# common_power.net
KiCad netlist of a schematic drawn in Altium Designer
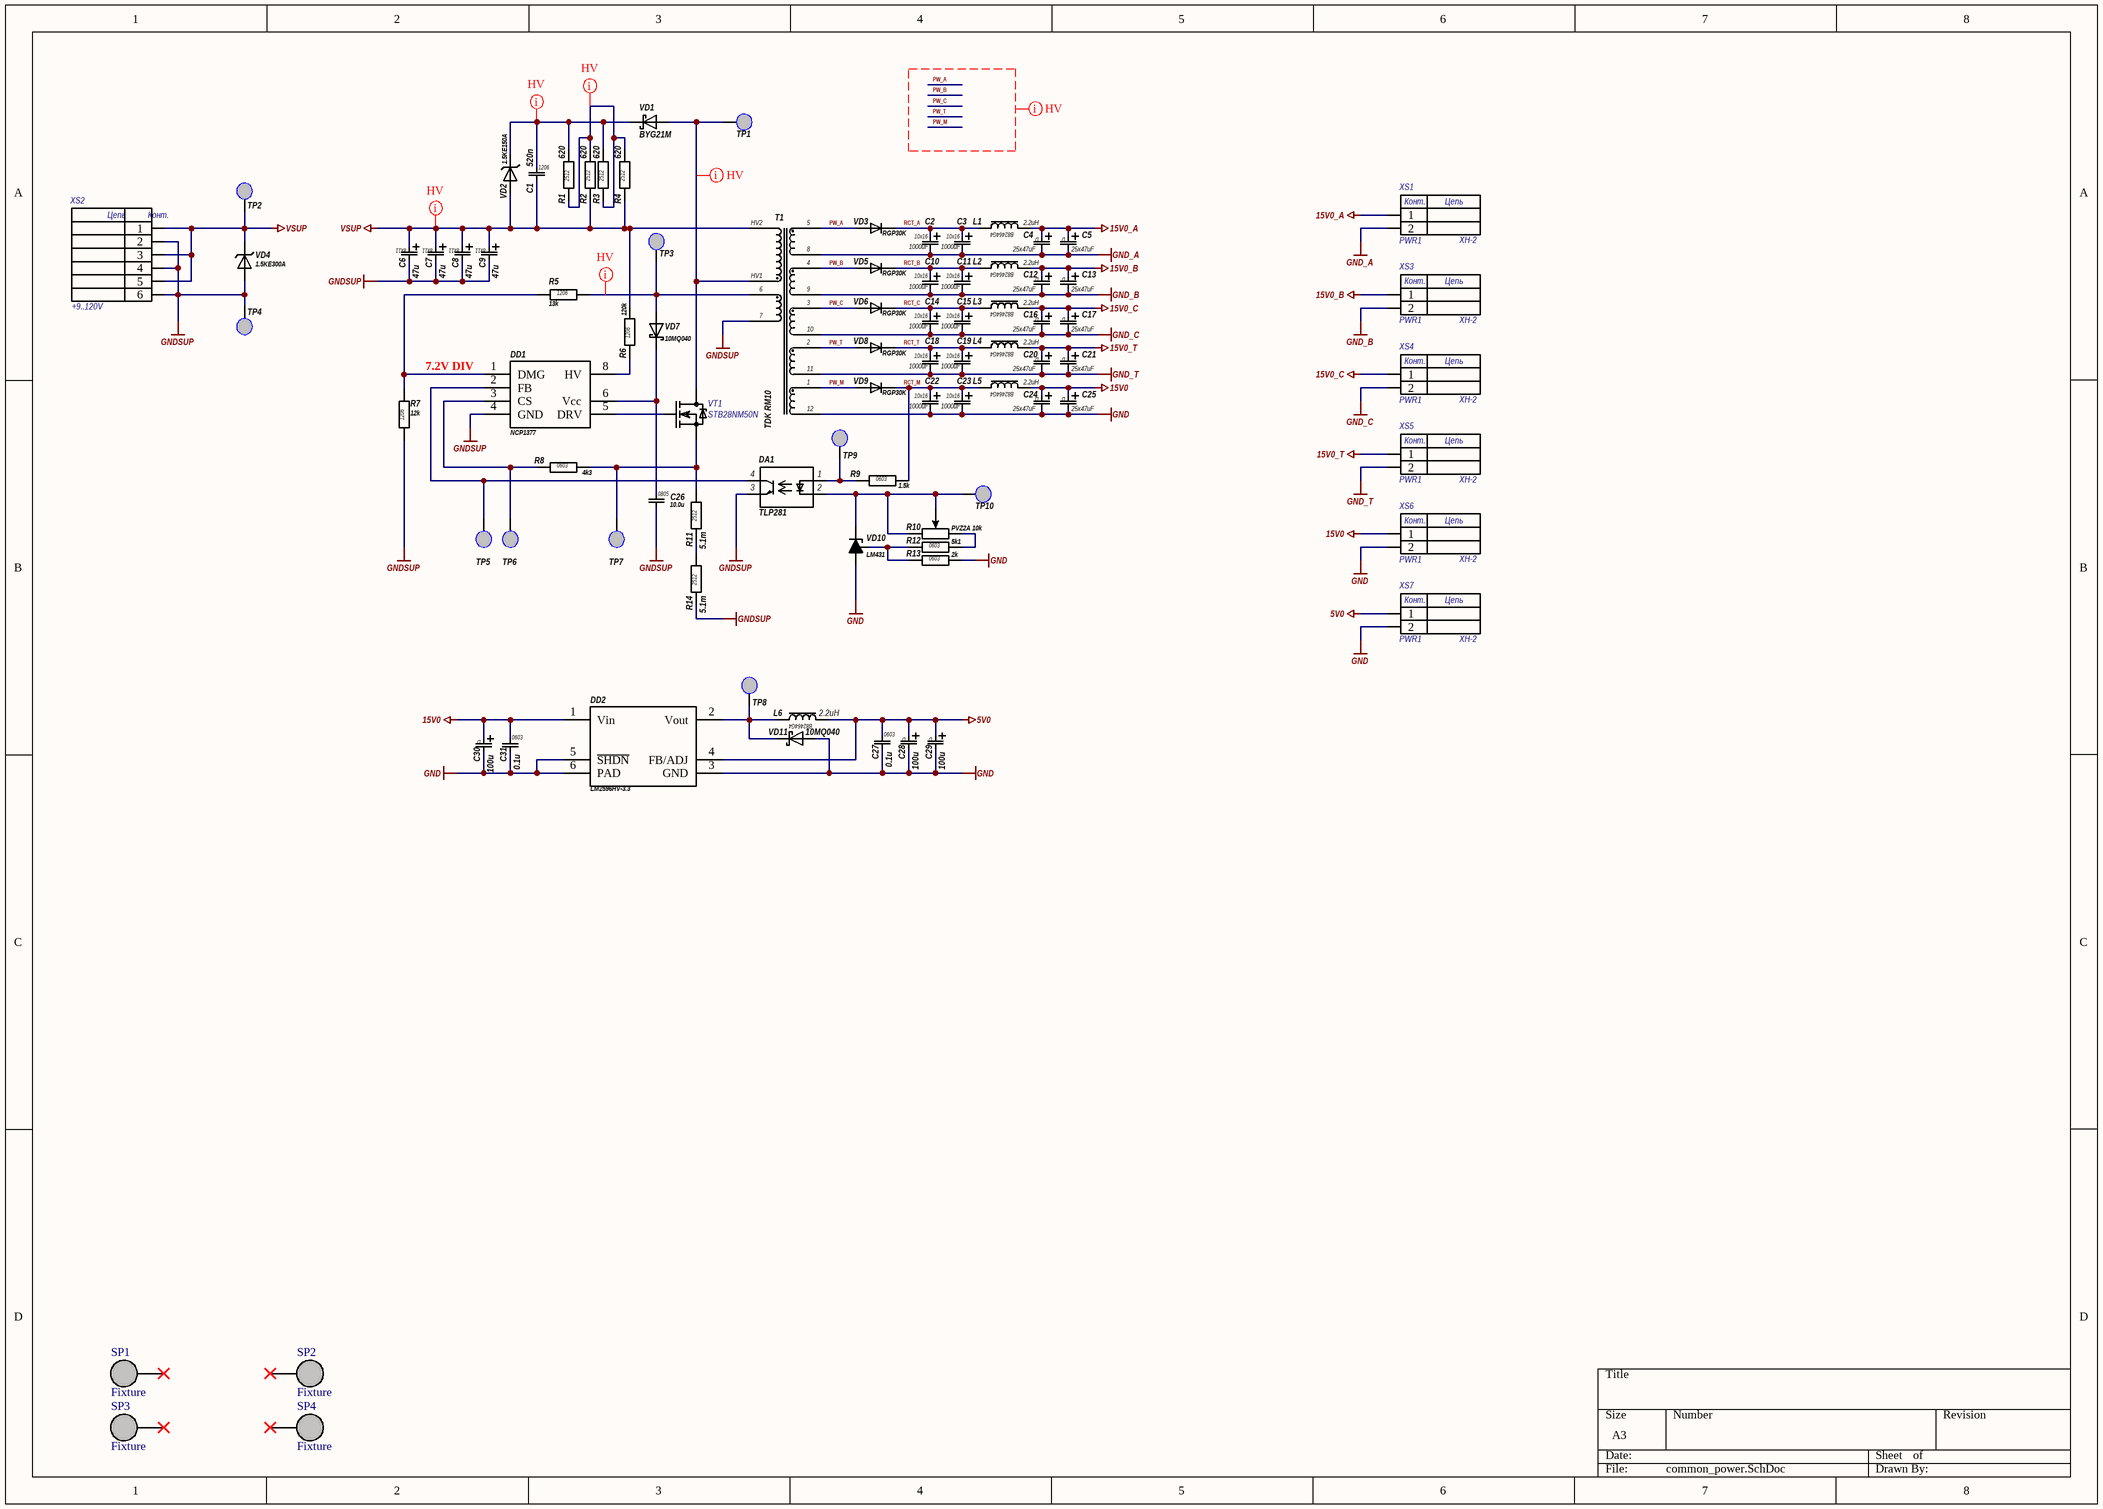
[diagram p0: common_power.SchDoc]

(export (version "E")
  (design (tool "Eeschema 10.0.6"))
  (components
    (comp (ref "C1")
      (value "520n")
      (footprint "CAP1206")
      (description "Конденсатор чип")
      (libsource (lib "EwgPassive") (part "CAP_1206"))
    )
    (comp (ref "C2")
      (value "1000uF")
      (footprint "ECAP_10x16")
      (description "Конденсатор электролитический")
      (libsource (lib "EwgPassive") (part "CAP_10x16"))
    )
    (comp (ref "C3")
      (value "1000uF")
      (footprint "ECAP_10x16")
      (description "Конденсатор электролитический")
      (libsource (lib "EwgPassive") (part "CAP_10x16"))
    )
    (comp (ref "C4")
      (value "25x47uF")
      (footprint "CAP_D")
      (description "Конденсатор танталовый")
      (libsource (lib "EwgPassive") (part "CAP_D"))
    )
    (comp (ref "C5")
      (value "25x47uF")
      (footprint "CAP_D")
      (description "Конденсатор танталовый")
      (libsource (lib "EwgPassive") (part "CAP_D"))
    )
    (comp (ref "C6")
      (value "47u")
      (footprint "B41828 8X11.5")
      (description "Конденсатор электролитический")
      (libsource (lib "EwgPassive") (part "CAP_B41828 8X11.5"))
    )
    (comp (ref "C7")
      (value "47u")
      (footprint "B41828 8X11.5")
      (description "Конденсатор электролитический")
      (libsource (lib "EwgPassive") (part "CAP_B41828 8X11.5"))
    )
    (comp (ref "C8")
      (value "47u")
      (footprint "B41828 8X11.5")
      (description "Конденсатор электролитический")
      (libsource (lib "EwgPassive") (part "CAP_B41828 8X11.5"))
    )
    (comp (ref "C9")
      (value "47u")
      (footprint "B41828 8X11.5")
      (description "Конденсатор электролитический")
      (libsource (lib "EwgPassive") (part "CAP_B41828 8X11.5"))
    )
    (comp (ref "C10")
      (value "1000uF")
      (footprint "ECAP_10x16")
      (description "Конденсатор электролитический")
      (libsource (lib "EwgPassive") (part "CAP_10x16"))
    )
    (comp (ref "C11")
      (value "1000uF")
      (footprint "ECAP_10x16")
      (description "Конденсатор электролитический")
      (libsource (lib "EwgPassive") (part "CAP_10x16"))
    )
    (comp (ref "C12")
      (value "25x47uF")
      (footprint "CAP_D")
      (description "Конденсатор танталовый")
      (libsource (lib "EwgPassive") (part "CAP_D"))
    )
    (comp (ref "C13")
      (value "25x47uF")
      (footprint "CAP_D")
      (description "Конденсатор танталовый")
      (libsource (lib "EwgPassive") (part "CAP_D"))
    )
    (comp (ref "C14")
      (value "1000uF")
      (footprint "ECAP_10x16")
      (description "Конденсатор электролитический")
      (libsource (lib "EwgPassive") (part "CAP_10x16"))
    )
    (comp (ref "C15")
      (value "1000uF")
      (footprint "ECAP_10x16")
      (description "Конденсатор электролитический")
      (libsource (lib "EwgPassive") (part "CAP_10x16"))
    )
    (comp (ref "C16")
      (value "25x47uF")
      (footprint "CAP_D")
      (description "Конденсатор танталовый")
      (libsource (lib "EwgPassive") (part "CAP_D"))
    )
    (comp (ref "C17")
      (value "25x47uF")
      (footprint "CAP_D")
      (description "Конденсатор танталовый")
      (libsource (lib "EwgPassive") (part "CAP_D"))
    )
    (comp (ref "C18")
      (value "1000uF")
      (footprint "ECAP_10x16")
      (description "Конденсатор электролитический")
      (libsource (lib "EwgPassive") (part "CAP_10x16"))
    )
    (comp (ref "C19")
      (value "1000uF")
      (footprint "ECAP_10x16")
      (description "Конденсатор электролитический")
      (libsource (lib "EwgPassive") (part "CAP_10x16"))
    )
    (comp (ref "C20")
      (value "25x47uF")
      (footprint "CAP_D")
      (description "Конденсатор танталовый")
      (libsource (lib "EwgPassive") (part "CAP_D"))
    )
    (comp (ref "C21")
      (value "25x47uF")
      (footprint "CAP_D")
      (description "Конденсатор танталовый")
      (libsource (lib "EwgPassive") (part "CAP_D"))
    )
    (comp (ref "C22")
      (value "1000uF")
      (footprint "ECAP_10x16")
      (description "Конденсатор электролитический")
      (libsource (lib "EwgPassive") (part "CAP_10x16"))
    )
    (comp (ref "C23")
      (value "1000uF")
      (footprint "ECAP_10x16")
      (description "Конденсатор электролитический")
      (libsource (lib "EwgPassive") (part "CAP_10x16"))
    )
    (comp (ref "C24")
      (value "25x47uF")
      (footprint "CAP_D")
      (description "Конденсатор танталовый")
      (libsource (lib "EwgPassive") (part "CAP_D"))
    )
    (comp (ref "C25")
      (value "25x47uF")
      (footprint "CAP_D")
      (description "Конденсатор танталовый")
      (libsource (lib "EwgPassive") (part "CAP_D"))
    )
    (comp (ref "C26")
      (value "10.0u")
      (footprint "CAP0805")
      (description "Конденсатор чип")
      (libsource (lib "EwgPassive") (part "CAP_0805"))
    )
    (comp (ref "C27")
      (value "0.1u")
      (footprint "CAP0603")
      (description "Конденсатор чип")
      (libsource (lib "EwgPassive") (part "CAP_0603"))
    )
    (comp (ref "C28")
      (value "100u")
      (footprint "CAP_D")
      (description "Конденсатор танталовый")
      (libsource (lib "EwgPassive") (part "CAP_D"))
    )
    (comp (ref "C29")
      (value "100u")
      (footprint "CAP_D")
      (description "Конденсатор танталовый")
      (libsource (lib "EwgPassive") (part "CAP_D"))
    )
    (comp (ref "C30")
      (value "100u")
      (footprint "CAP_D")
      (description "Конденсатор танталовый")
      (libsource (lib "EwgPassive") (part "CAP_D"))
    )
    (comp (ref "C31")
      (value "0.1u")
      (footprint "CAP0603")
      (description "Конденсатор чип")
      (libsource (lib "EwgPassive") (part "CAP_0603"))
    )
    (comp (ref "DA1")
      (value "TLP281")
      (footprint "SOIC-4")
      (description "Оптопара")
      (libsource (lib "EwgOpto") (part "TPL281-1"))
    )
    (comp (ref "DD1")
      (value "NCP1377")
      (footprint "SO8_NCP1377")
      (description "Контроллер обратноходового преобразователя")
      (libsource (lib "EwgMicrochips") (part "NCP1377"))
    )
    (comp (ref "DD2")
      (value "LM2596HV-3.3")
      (footprint "TO-263-5")
      (description "Понижающий DC-DC преобразователь с широким диапазоном входного напряжения (Vin=4.5..60V)")
      (libsource (lib "EwgMicrochips") (part "LM2596HV-x.x"))
    )
    (comp (ref "L1")
      (value "2.2uH")
      (footprint "B82464G4")
      (description "Индуктивность чип")
      (libsource (lib "EwgPassive") (part "IND_B82464G4"))
    )
    (comp (ref "L2")
      (value "2.2uH")
      (footprint "B82464G4")
      (description "Индуктивность чип")
      (libsource (lib "EwgPassive") (part "IND_B82464G4"))
    )
    (comp (ref "L3")
      (value "2.2uH")
      (footprint "B82464G4")
      (description "Индуктивность чип")
      (libsource (lib "EwgPassive") (part "IND_B82464G4"))
    )
    (comp (ref "L4")
      (value "2.2uH")
      (footprint "B82464G4")
      (description "Индуктивность чип")
      (libsource (lib "EwgPassive") (part "IND_B82464G4"))
    )
    (comp (ref "L5")
      (value "2.2uH")
      (footprint "B82464G4")
      (description "Индуктивность чип")
      (libsource (lib "EwgPassive") (part "IND_B82464G4"))
    )
    (comp (ref "L6")
      (value "2.2uH")
      (footprint "B82464G4")
      (description "Индуктивность чип")
      (libsource (lib "EwgPassive") (part "IND_B82464G4"))
    )
    (comp (ref "R1")
      (value "620")
      (footprint "RES2512")
      (description "Резистор чип")
      (libsource (lib "EwgPassive") (part "RES_2512"))
    )
    (comp (ref "R2")
      (value "620")
      (footprint "RES2512")
      (description "Резистор чип")
      (libsource (lib "EwgPassive") (part "RES_2512"))
    )
    (comp (ref "R3")
      (value "620")
      (footprint "RES2512")
      (description "Резистор чип")
      (libsource (lib "EwgPassive") (part "RES_2512"))
    )
    (comp (ref "R4")
      (value "620")
      (footprint "RES2512")
      (description "Резистор чип")
      (libsource (lib "EwgPassive") (part "RES_2512"))
    )
    (comp (ref "R5")
      (value "13k")
      (footprint "RES1206")
      (description "Резистор чип")
      (libsource (lib "") (part "RES_1206_1"))
    )
    (comp (ref "R6")
      (value "120k")
      (footprint "RES1206")
      (description "Резистор чип")
      (libsource (lib "EwgPassive") (part "RES_1206"))
    )
    (comp (ref "R7")
      (value "12k")
      (footprint "RES1206")
      (description "Резистор чип")
      (libsource (lib "EwgPassive") (part "RES_1206"))
    )
    (comp (ref "R8")
      (value "4k3")
      (footprint "RES0603")
      (description "Резистор чип")
      (libsource (lib "EwgPassive") (part "RES_0603"))
    )
    (comp (ref "R9")
      (value "1.5k")
      (footprint "RES0603")
      (description "Резистор чип")
      (libsource (lib "EwgPassive") (part "RES_0603"))
    )
    (comp (ref "R10")
      (value "PVZ2A 10k")
      (footprint "PVZ2A")
      (description "Резистор подстроечный")
      (libsource (lib "EwgPassive") (part "PVZ2A"))
    )
    (comp (ref "R11")
      (value "5.1m")
      (footprint "RES2512")
      (description "Резистор чип")
      (libsource (lib "EwgPassive") (part "RES_2512"))
    )
    (comp (ref "R12")
      (value "5k1")
      (footprint "RES0603")
      (description "Резистор чип")
      (libsource (lib "EwgPassive") (part "RES_0603"))
    )
    (comp (ref "R13")
      (value "2k")
      (footprint "RES0603")
      (description "Резистор чип")
      (libsource (lib "EwgPassive") (part "RES_0603"))
    )
    (comp (ref "R14")
      (value "5.1m")
      (footprint "RES2512")
      (description "Резистор чип")
      (libsource (lib "EwgPassive") (part "RES_2512"))
    )
    (comp (ref "SP1")
      (value "Fixture")
      (footprint "FIXTURE_HOLE_3mm")
      (description "Structural screw pad")
      (libsource (lib "EwgConnectors") (part "Structural Pad"))
    )
    (comp (ref "SP2")
      (value "Fixture")
      (footprint "FIXTURE_HOLE_3mm")
      (description "Structural screw pad")
      (libsource (lib "EwgConnectors") (part "Structural Pad"))
    )
    (comp (ref "SP3")
      (value "Fixture")
      (footprint "FIXTURE_HOLE_3mm")
      (description "Structural screw pad")
      (libsource (lib "EwgConnectors") (part "Structural Pad"))
    )
    (comp (ref "SP4")
      (value "Fixture")
      (footprint "FIXTURE_HOLE_3mm")
      (description "Structural screw pad")
      (libsource (lib "EwgConnectors") (part "Structural Pad"))
    )
    (comp (ref "T1")
      (value "TDK RM10")
      (footprint "TDK RM8 HV ADD")
      (libsource (lib "EwgPassive") (part "TRANS_Flyback_MDrive"))
    )
    (comp (ref "TP1")
      (value "Test point")
      (footprint "TESTPOINT_HOLE")
      (libsource (lib "EwgPassive") (part "Test point"))
    )
    (comp (ref "TP2")
      (value "Test point")
      (footprint "TESTPOINT_HOLE")
      (libsource (lib "EwgPassive") (part "Test point"))
    )
    (comp (ref "TP3")
      (value "Test point")
      (footprint "TESTPOINT_HOLE")
      (libsource (lib "EwgPassive") (part "Test point"))
    )
    (comp (ref "TP4")
      (value "Test point")
      (footprint "TESTPOINT_HOLE")
      (libsource (lib "EwgPassive") (part "Test point"))
    )
    (comp (ref "TP5")
      (value "Test point")
      (footprint "TESTPOINT_HOLE")
      (libsource (lib "EwgPassive") (part "Test point"))
    )
    (comp (ref "TP6")
      (value "Test point")
      (footprint "TESTPOINT_HOLE")
      (libsource (lib "EwgPassive") (part "Test point"))
    )
    (comp (ref "TP7")
      (value "Test point")
      (footprint "TESTPOINT_HOLE")
      (libsource (lib "EwgPassive") (part "Test point"))
    )
    (comp (ref "TP8")
      (value "Test point")
      (footprint "TESTPOINT_HOLE")
      (libsource (lib "EwgPassive") (part "Test point"))
    )
    (comp (ref "TP9")
      (value "Test point")
      (footprint "TESTPOINT_HOLE")
      (libsource (lib "EwgPassive") (part "Test point"))
    )
    (comp (ref "TP10")
      (value "Test point")
      (footprint "TESTPOINT_HOLE")
      (libsource (lib "EwgPassive") (part "Test point"))
    )
    (comp (ref "VD1")
      (value "BYG21M")
      (footprint "SMA")
      (description "Диод Шоттки")
      (libsource (lib "EwgActive") (part "SX34"))
    )
    (comp (ref "VD2")
      (value "1.5KE150A")
      (footprint "DO-27")
      (description "Диод TVS")
      (libsource (lib "EwgActive") (part "1.5KExxxA"))
    )
    (comp (ref "VD3")
      (value "RGP30K")
      (footprint "DO-201_H")
      (description "Диод выпрямительный 800В 3А")
      (libsource (lib "EwgActive") (part "RGP30K"))
    )
    (comp (ref "VD4")
      (value "1.5KE300A")
      (footprint "DO-27")
      (description "Диод TVS")
      (libsource (lib "EwgActive") (part "1.5KExxxA"))
    )
    (comp (ref "VD5")
      (value "RGP30K")
      (footprint "DO-201_H")
      (description "Диод выпрямительный 800В 3А")
      (libsource (lib "EwgActive") (part "RGP30K"))
    )
    (comp (ref "VD6")
      (value "RGP30K")
      (footprint "DO-201_H")
      (description "Диод выпрямительный 800В 3А")
      (libsource (lib "EwgActive") (part "RGP30K"))
    )
    (comp (ref "VD7")
      (value "10MQ040")
      (footprint "SMA")
      (description "Диод Шоттки")
      (libsource (lib "EwgActive") (part "10MQ040"))
    )
    (comp (ref "VD8")
      (value "RGP30K")
      (footprint "DO-201_H")
      (description "Диод выпрямительный 800В 3А")
      (libsource (lib "EwgActive") (part "RGP30K"))
    )
    (comp (ref "VD9")
      (value "RGP30K")
      (footprint "DO-201_H")
      (description "Диод выпрямительный 800В 3А")
      (libsource (lib "EwgActive") (part "RGP30K"))
    )
    (comp (ref "VD10")
      (value "LM431")
      (footprint "SOT23-3")
      (description "Программируемый стабилитрон")
      (libsource (lib "EwgActive") (part "LM431"))
    )
    (comp (ref "VD11")
      (value "10MQ040")
      (footprint "SMA")
      (description "Диод Шоттки")
      (libsource (lib "EwgActive") (part "10MQ040"))
    )
    (comp (ref "VT1")
      (value "STB28NM50N")
      (footprint "D2PAK")
      (description "Транзистор полевой (MOSFET)")
      (libsource (lib "EwgActive") (part "IRF2807"))
    )
    (comp (ref "XS1")
      (value "XH-2")
      (footprint "XH-2")
      (description "Разъем")
      (fields (field (name "ALTIUM_VALUE") "PWR1"))
      (libsource (lib "EwgConnectors") (part "CONN_MW-2M"))
    )
    (comp (ref "XS2")
      (value "+9..120V")
      (footprint "MF2X3R_FIX")
      (description "Разъем")
      (libsource (lib "EwgConnectors") (part "MF2X3R_FIX"))
    )
    (comp (ref "XS3")
      (value "XH-2")
      (footprint "XH-2")
      (description "Разъем")
      (fields (field (name "ALTIUM_VALUE") "PWR1"))
      (libsource (lib "EwgConnectors") (part "CONN_MW-2M"))
    )
    (comp (ref "XS4")
      (value "XH-2")
      (footprint "XH-2")
      (description "Разъем")
      (fields (field (name "ALTIUM_VALUE") "PWR1"))
      (libsource (lib "EwgConnectors") (part "CONN_MW-2M"))
    )
    (comp (ref "XS5")
      (value "XH-2")
      (footprint "XH-2")
      (description "Разъем")
      (fields (field (name "ALTIUM_VALUE") "PWR1"))
      (libsource (lib "EwgConnectors") (part "CONN_MW-2M"))
    )
    (comp (ref "XS6")
      (value "XH-2")
      (footprint "XH-2")
      (description "Разъем")
      (fields (field (name "ALTIUM_VALUE") "PWR1"))
      (libsource (lib "EwgConnectors") (part "CONN_MW-2M"))
    )
    (comp (ref "XS7")
      (value "XH-2")
      (footprint "XH-2")
      (description "Разъем")
      (fields (field (name "ALTIUM_VALUE") "PWR1"))
      (libsource (lib "EwgConnectors") (part "CONN_MW-2M"))
    )
  )
  (nets
    (net (code "1") (name "/PW_A") (class "Default")
      (node (ref "T1") (pin "5") (pinfunction "5_5") (pintype "passive"))
      (node (ref "VD3") (pin "A") (pintype "passive"))
    )
    (net (code "2") (name "/PW_B") (class "Default")
      (node (ref "T1") (pin "4") (pinfunction "4_4") (pintype "passive"))
      (node (ref "VD5") (pin "A") (pintype "passive"))
    )
    (net (code "3") (name "/PW_C") (class "Default")
      (node (ref "T1") (pin "3") (pinfunction "3_3") (pintype "passive"))
      (node (ref "VD6") (pin "A") (pintype "passive"))
    )
    (net (code "4") (name "/PW_M") (class "Default")
      (node (ref "T1") (pin "1") (pinfunction "1_1") (pintype "passive"))
      (node (ref "VD9") (pin "A") (pintype "passive"))
    )
    (net (code "5") (name "/PW_T") (class "Default")
      (node (ref "T1") (pin "2") (pinfunction "2_2") (pintype "passive"))
      (node (ref "VD8") (pin "A") (pintype "passive"))
    )
    (net (code "6") (name "/RCT_A") (class "Default")
      (node (ref "C2") (pin "1") (pintype "passive"))
      (node (ref "C3") (pin "1") (pintype "passive"))
      (node (ref "L1") (pin "1") (pintype "passive"))
      (node (ref "VD3") (pin "K") (pintype "passive"))
    )
    (net (code "7") (name "/RCT_B") (class "Default")
      (node (ref "C10") (pin "1") (pintype "passive"))
      (node (ref "C11") (pin "1") (pintype "passive"))
      (node (ref "L2") (pin "1") (pintype "passive"))
      (node (ref "VD5") (pin "K") (pintype "passive"))
    )
    (net (code "8") (name "/RCT_C") (class "Default")
      (node (ref "C14") (pin "1") (pintype "passive"))
      (node (ref "C15") (pin "1") (pintype "passive"))
      (node (ref "L3") (pin "1") (pintype "passive"))
      (node (ref "VD6") (pin "K") (pintype "passive"))
    )
    (net (code "9") (name "/RCT_M") (class "Default")
      (node (ref "C22") (pin "1") (pintype "passive"))
      (node (ref "C23") (pin "1") (pintype "passive"))
      (node (ref "L5") (pin "1") (pintype "passive"))
      (node (ref "R9") (pin "2") (pintype "passive"))
      (node (ref "VD9") (pin "K") (pintype "passive"))
    )
    (net (code "10") (name "/RCT_T") (class "Default")
      (node (ref "C18") (pin "1") (pintype "passive"))
      (node (ref "C19") (pin "1") (pintype "passive"))
      (node (ref "L4") (pin "1") (pintype "passive"))
      (node (ref "VD8") (pin "K") (pintype "passive"))
    )
    (net (code "11") (name "5V0") (class "Default")
      (node (ref "C27") (pin "1") (pintype "passive"))
      (node (ref "C28") (pin "1") (pintype "passive"))
      (node (ref "C29") (pin "1") (pintype "passive"))
      (node (ref "DD2") (pin "4") (pinfunction "FB/ADJ_4") (pintype "passive"))
      (node (ref "L6") (pin "2") (pintype "passive"))
      (node (ref "XS7") (pin "1") (pinfunction "1_1") (pintype "passive"))
    )
    (net (code "12") (name "15V0") (class "Default")
      (node (ref "C24") (pin "1") (pintype "passive"))
      (node (ref "C25") (pin "1") (pintype "passive"))
      (node (ref "C30") (pin "1") (pintype "passive"))
      (node (ref "C31") (pin "1") (pintype "passive"))
      (node (ref "DD2") (pin "1") (pinfunction "Vin_1") (pintype "passive"))
      (node (ref "L5") (pin "2") (pintype "passive"))
      (node (ref "XS6") (pin "1") (pinfunction "1_1") (pintype "passive"))
    )
    (net (code "13") (name "15V0_A") (class "Default")
      (node (ref "C4") (pin "1") (pintype "passive"))
      (node (ref "C5") (pin "1") (pintype "passive"))
      (node (ref "L1") (pin "2") (pintype "passive"))
      (node (ref "XS1") (pin "1") (pinfunction "1_1") (pintype "passive"))
    )
    (net (code "14") (name "15V0_B") (class "Default")
      (node (ref "C12") (pin "1") (pintype "passive"))
      (node (ref "C13") (pin "1") (pintype "passive"))
      (node (ref "L2") (pin "2") (pintype "passive"))
      (node (ref "XS3") (pin "1") (pinfunction "1_1") (pintype "passive"))
    )
    (net (code "15") (name "15V0_C") (class "Default")
      (node (ref "C16") (pin "1") (pintype "passive"))
      (node (ref "C17") (pin "1") (pintype "passive"))
      (node (ref "L3") (pin "2") (pintype "passive"))
      (node (ref "XS4") (pin "1") (pinfunction "1_1") (pintype "passive"))
    )
    (net (code "16") (name "15V0_T") (class "Default")
      (node (ref "C20") (pin "1") (pintype "passive"))
      (node (ref "C21") (pin "1") (pintype "passive"))
      (node (ref "L4") (pin "2") (pintype "passive"))
      (node (ref "XS5") (pin "1") (pinfunction "1_1") (pintype "passive"))
    )
    (net (code "17") (name "GND") (class "Default")
      (node (ref "C22") (pin "2") (pintype "passive"))
      (node (ref "C23") (pin "2") (pintype "passive"))
      (node (ref "C24") (pin "2") (pintype "passive"))
      (node (ref "C25") (pin "2") (pintype "passive"))
      (node (ref "C27") (pin "2") (pintype "passive"))
      (node (ref "C28") (pin "2") (pintype "passive"))
      (node (ref "C29") (pin "2") (pintype "passive"))
      (node (ref "C30") (pin "2") (pintype "passive"))
      (node (ref "C31") (pin "2") (pintype "passive"))
      (node (ref "DD2") (pin "3") (pinfunction "GND_3") (pintype "passive"))
      (node (ref "DD2") (pin "5") (pinfunction "~{SHDN}_5") (pintype "passive"))
      (node (ref "DD2") (pin "6") (pinfunction "PAD_6") (pintype "passive"))
      (node (ref "R13") (pin "2") (pintype "passive"))
      (node (ref "T1") (pin "12") (pinfunction "12_12") (pintype "passive"))
      (node (ref "VD10") (pin "3") (pintype "passive"))
      (node (ref "VD11") (pin "1") (pintype "passive"))
      (node (ref "XS6") (pin "2") (pinfunction "2_2") (pintype "passive"))
      (node (ref "XS7") (pin "2") (pinfunction "2_2") (pintype "passive"))
    )
    (net (code "18") (name "GNDSUP") (class "Default")
      (node (ref "C26") (pin "2") (pintype "passive"))
      (node (ref "C6") (pin "2") (pintype "passive"))
      (node (ref "C7") (pin "2") (pintype "passive"))
      (node (ref "C8") (pin "2") (pintype "passive"))
      (node (ref "C9") (pin "2") (pintype "passive"))
      (node (ref "DA1") (pin "3") (pintype "passive"))
      (node (ref "DD1") (pin "4") (pinfunction "GND_4") (pintype "passive"))
      (node (ref "R14") (pin "1") (pintype "passive"))
      (node (ref "R7") (pin "1") (pintype "passive"))
      (node (ref "T1") (pin "7") (pinfunction "7_7") (pintype "passive"))
      (node (ref "TP4") (pin "1") (pinfunction "TP_1") (pintype "passive"))
      (node (ref "VD4") (pin "A") (pintype "passive"))
      (node (ref "XS2") (pin "2") (pinfunction "2_2") (pintype "passive"))
      (node (ref "XS2") (pin "4") (pinfunction "4_4") (pintype "passive"))
      (node (ref "XS2") (pin "6") (pinfunction "6_6") (pintype "passive"))
    )
    (net (code "19") (name "GND_A") (class "Default")
      (node (ref "C2") (pin "2") (pintype "passive"))
      (node (ref "C3") (pin "2") (pintype "passive"))
      (node (ref "C4") (pin "2") (pintype "passive"))
      (node (ref "C5") (pin "2") (pintype "passive"))
      (node (ref "T1") (pin "8") (pinfunction "8_8") (pintype "passive"))
      (node (ref "XS1") (pin "2") (pinfunction "2_2") (pintype "passive"))
    )
    (net (code "20") (name "GND_B") (class "Default")
      (node (ref "C10") (pin "2") (pintype "passive"))
      (node (ref "C11") (pin "2") (pintype "passive"))
      (node (ref "C12") (pin "2") (pintype "passive"))
      (node (ref "C13") (pin "2") (pintype "passive"))
      (node (ref "T1") (pin "9") (pinfunction "9_9") (pintype "passive"))
      (node (ref "XS3") (pin "2") (pinfunction "2_2") (pintype "passive"))
    )
    (net (code "21") (name "GND_C") (class "Default")
      (node (ref "C14") (pin "2") (pintype "passive"))
      (node (ref "C15") (pin "2") (pintype "passive"))
      (node (ref "C16") (pin "2") (pintype "passive"))
      (node (ref "C17") (pin "2") (pintype "passive"))
      (node (ref "T1") (pin "10") (pinfunction "10_10") (pintype "passive"))
      (node (ref "XS4") (pin "2") (pinfunction "2_2") (pintype "passive"))
    )
    (net (code "22") (name "GND_T") (class "Default")
      (node (ref "C18") (pin "2") (pintype "passive"))
      (node (ref "C19") (pin "2") (pintype "passive"))
      (node (ref "C20") (pin "2") (pintype "passive"))
      (node (ref "C21") (pin "2") (pintype "passive"))
      (node (ref "T1") (pin "11") (pinfunction "11_11") (pintype "passive"))
      (node (ref "XS5") (pin "2") (pinfunction "2_2") (pintype "passive"))
    )
    (net (code "23") (name "Net-(C1-Pad1)") (class "Default")
      (node (ref "C1") (pin "1") (pintype "passive"))
      (node (ref "R1") (pin "2") (pintype "passive"))
      (node (ref "R3") (pin "2") (pintype "passive"))
      (node (ref "VD1") (pin "2") (pintype "passive"))
      (node (ref "VD2") (pin "K") (pintype "passive"))
    )
    (net (code "24") (name "Net-(DD1-CS)") (class "Default")
      (node (ref "DD1") (pin "3") (pinfunction "CS_3") (pintype "passive"))
      (node (ref "R8") (pin "1") (pintype "passive"))
      (node (ref "TP6") (pin "1") (pinfunction "TP_1") (pintype "passive"))
    )
    (net (code "25") (name "Net-(DD1-DMG)") (class "Default")
      (node (ref "DD1") (pin "1") (pinfunction "DMG_1") (pintype "passive"))
      (node (ref "R5") (pin "1") (pintype "passive"))
      (node (ref "R7") (pin "2") (pintype "passive"))
    )
    (net (code "26") (name "Net-(DD1-DRV)") (class "Default")
      (node (ref "DD1") (pin "5") (pinfunction "DRV_5") (pintype "passive"))
      (node (ref "VT1") (pin "1") (pinfunction "0_1") (pintype "passive"))
    )
    (net (code "27") (name "Net-(DD1-FB)") (class "Default")
      (node (ref "DA1") (pin "4") (pintype "passive"))
      (node (ref "DD1") (pin "2") (pinfunction "FB_2") (pintype "passive"))
      (node (ref "TP5") (pin "1") (pinfunction "TP_1") (pintype "passive"))
    )
    (net (code "28") (name "Net-(DD1-HV)") (class "Default")
      (node (ref "DD1") (pin "8") (pinfunction "HV_8") (pintype "passive"))
      (node (ref "R6") (pin "1") (pintype "passive"))
    )
    (net (code "29") (name "Net-(DD1-Vcc)") (class "Default")
      (node (ref "C26") (pin "1") (pintype "passive"))
      (node (ref "DD1") (pin "6") (pinfunction "Vcc_6") (pintype "passive"))
      (node (ref "VD7") (pin "2") (pintype "passive"))
    )
    (net (code "30") (name "Net-(DD2-Vout)") (class "Default")
      (node (ref "DD2") (pin "2") (pinfunction "Vout_2") (pintype "passive"))
      (node (ref "L6") (pin "1") (pintype "passive"))
      (node (ref "TP8") (pin "1") (pinfunction "TP_1") (pintype "passive"))
      (node (ref "VD11") (pin "2") (pintype "passive"))
    )
    (net (code "31") (name "Net-(R1-Pad1)") (class "Default")
      (node (ref "R1") (pin "1") (pintype "passive"))
      (node (ref "R2") (pin "2") (pintype "passive"))
      (node (ref "R3") (pin "1") (pintype "passive"))
      (node (ref "R4") (pin "2") (pintype "passive"))
    )
    (net (code "32") (name "Net-(R10-Pad3)") (class "Default")
      (node (ref "R10") (pin "3") (pintype "passive"))
      (node (ref "R12") (pin "2") (pintype "passive"))
    )
    (net (code "33") (name "Net-(R11-Pad1)") (class "Default")
      (node (ref "R11") (pin "1") (pintype "passive"))
      (node (ref "R14") (pin "2") (pintype "passive"))
    )
    (net (code "34") (name "Net-(R12-Pad1)") (class "Default")
      (node (ref "R12") (pin "1") (pintype "passive"))
      (node (ref "R13") (pin "1") (pintype "passive"))
      (node (ref "VD10") (pin "2") (pinfunction "2_2") (pintype "passive"))
    )
    (net (code "35") (name "Net-(T1-13)") (class "Default")
      (node (ref "T1") (pin "HV1") (pinfunction "13_HV1") (pintype "passive"))
      (node (ref "TP1") (pin "1") (pinfunction "TP_1") (pintype "passive"))
      (node (ref "VD1") (pin "1") (pintype "passive"))
      (node (ref "VT1") (pin "3") (pinfunction "2_3") (pintype "passive"))
    )
    (net (code "36") (name "Net-(TP3-TP)") (class "Default")
      (node (ref "R5") (pin "2") (pintype "passive"))
      (node (ref "T1") (pin "6") (pinfunction "6_6") (pintype "passive"))
      (node (ref "TP3") (pin "1") (pinfunction "TP_1") (pintype "passive"))
      (node (ref "VD7") (pin "1") (pintype "passive"))
    )
    (net (code "37") (name "Net-(TP7-TP)") (class "Default")
      (node (ref "R11") (pin "2") (pintype "passive"))
      (node (ref "R8") (pin "2") (pintype "passive"))
      (node (ref "TP7") (pin "1") (pinfunction "TP_1") (pintype "passive"))
      (node (ref "VT1") (pin "2") (pinfunction "1_2") (pintype "passive"))
    )
    (net (code "38") (name "Net-(TP9-TP)") (class "Default")
      (node (ref "DA1") (pin "1") (pintype "passive"))
      (node (ref "R9") (pin "1") (pintype "passive"))
      (node (ref "TP9") (pin "1") (pinfunction "TP_1") (pintype "passive"))
    )
    (net (code "39") (name "Net-(TP10-TP)") (class "Default")
      (node (ref "DA1") (pin "2") (pintype "passive"))
      (node (ref "R10") (pin "1") (pintype "passive"))
      (node (ref "R10") (pin "2") (pinfunction "2_2") (pintype "passive"))
      (node (ref "TP10") (pin "1") (pinfunction "TP_1") (pintype "passive"))
      (node (ref "VD10") (pin "1") (pintype "passive"))
    )
    (net (code "40") (name "VSUP") (class "Default")
      (node (ref "C1") (pin "2") (pintype "passive"))
      (node (ref "C6") (pin "1") (pintype "passive"))
      (node (ref "C7") (pin "1") (pintype "passive"))
      (node (ref "C8") (pin "1") (pintype "passive"))
      (node (ref "C9") (pin "1") (pintype "passive"))
      (node (ref "R2") (pin "1") (pintype "passive"))
      (node (ref "R4") (pin "1") (pintype "passive"))
      (node (ref "R6") (pin "2") (pintype "passive"))
      (node (ref "T1") (pin "HV2") (pinfunction "14_HV2") (pintype "passive"))
      (node (ref "TP2") (pin "1") (pinfunction "TP_1") (pintype "passive"))
      (node (ref "VD2") (pin "A") (pintype "passive"))
      (node (ref "VD4") (pin "K") (pintype "passive"))
      (node (ref "XS2") (pin "1") (pinfunction "1_1") (pintype "passive"))
      (node (ref "XS2") (pin "3") (pinfunction "3_3") (pintype "passive"))
      (node (ref "XS2") (pin "5") (pinfunction "5_5") (pintype "passive"))
    )
    (net (code "41") (name "unconnected-(SP1-PadS)") (class "Default")
      (node (ref "SP1") (pin "S") (pinfunction "S_S") (pintype "passive+no_connect"))
    )
    (net (code "42") (name "unconnected-(SP2-PadS)") (class "Default")
      (node (ref "SP2") (pin "S") (pinfunction "S_S") (pintype "passive+no_connect"))
    )
    (net (code "43") (name "unconnected-(SP3-PadS)") (class "Default")
      (node (ref "SP3") (pin "S") (pinfunction "S_S") (pintype "passive+no_connect"))
    )
    (net (code "44") (name "unconnected-(SP4-PadS)") (class "Default")
      (node (ref "SP4") (pin "S") (pinfunction "S_S") (pintype "passive+no_connect"))
    )
  )
)
